# kraken.net
KiCad netlist of a schematic drawn in EAGLE
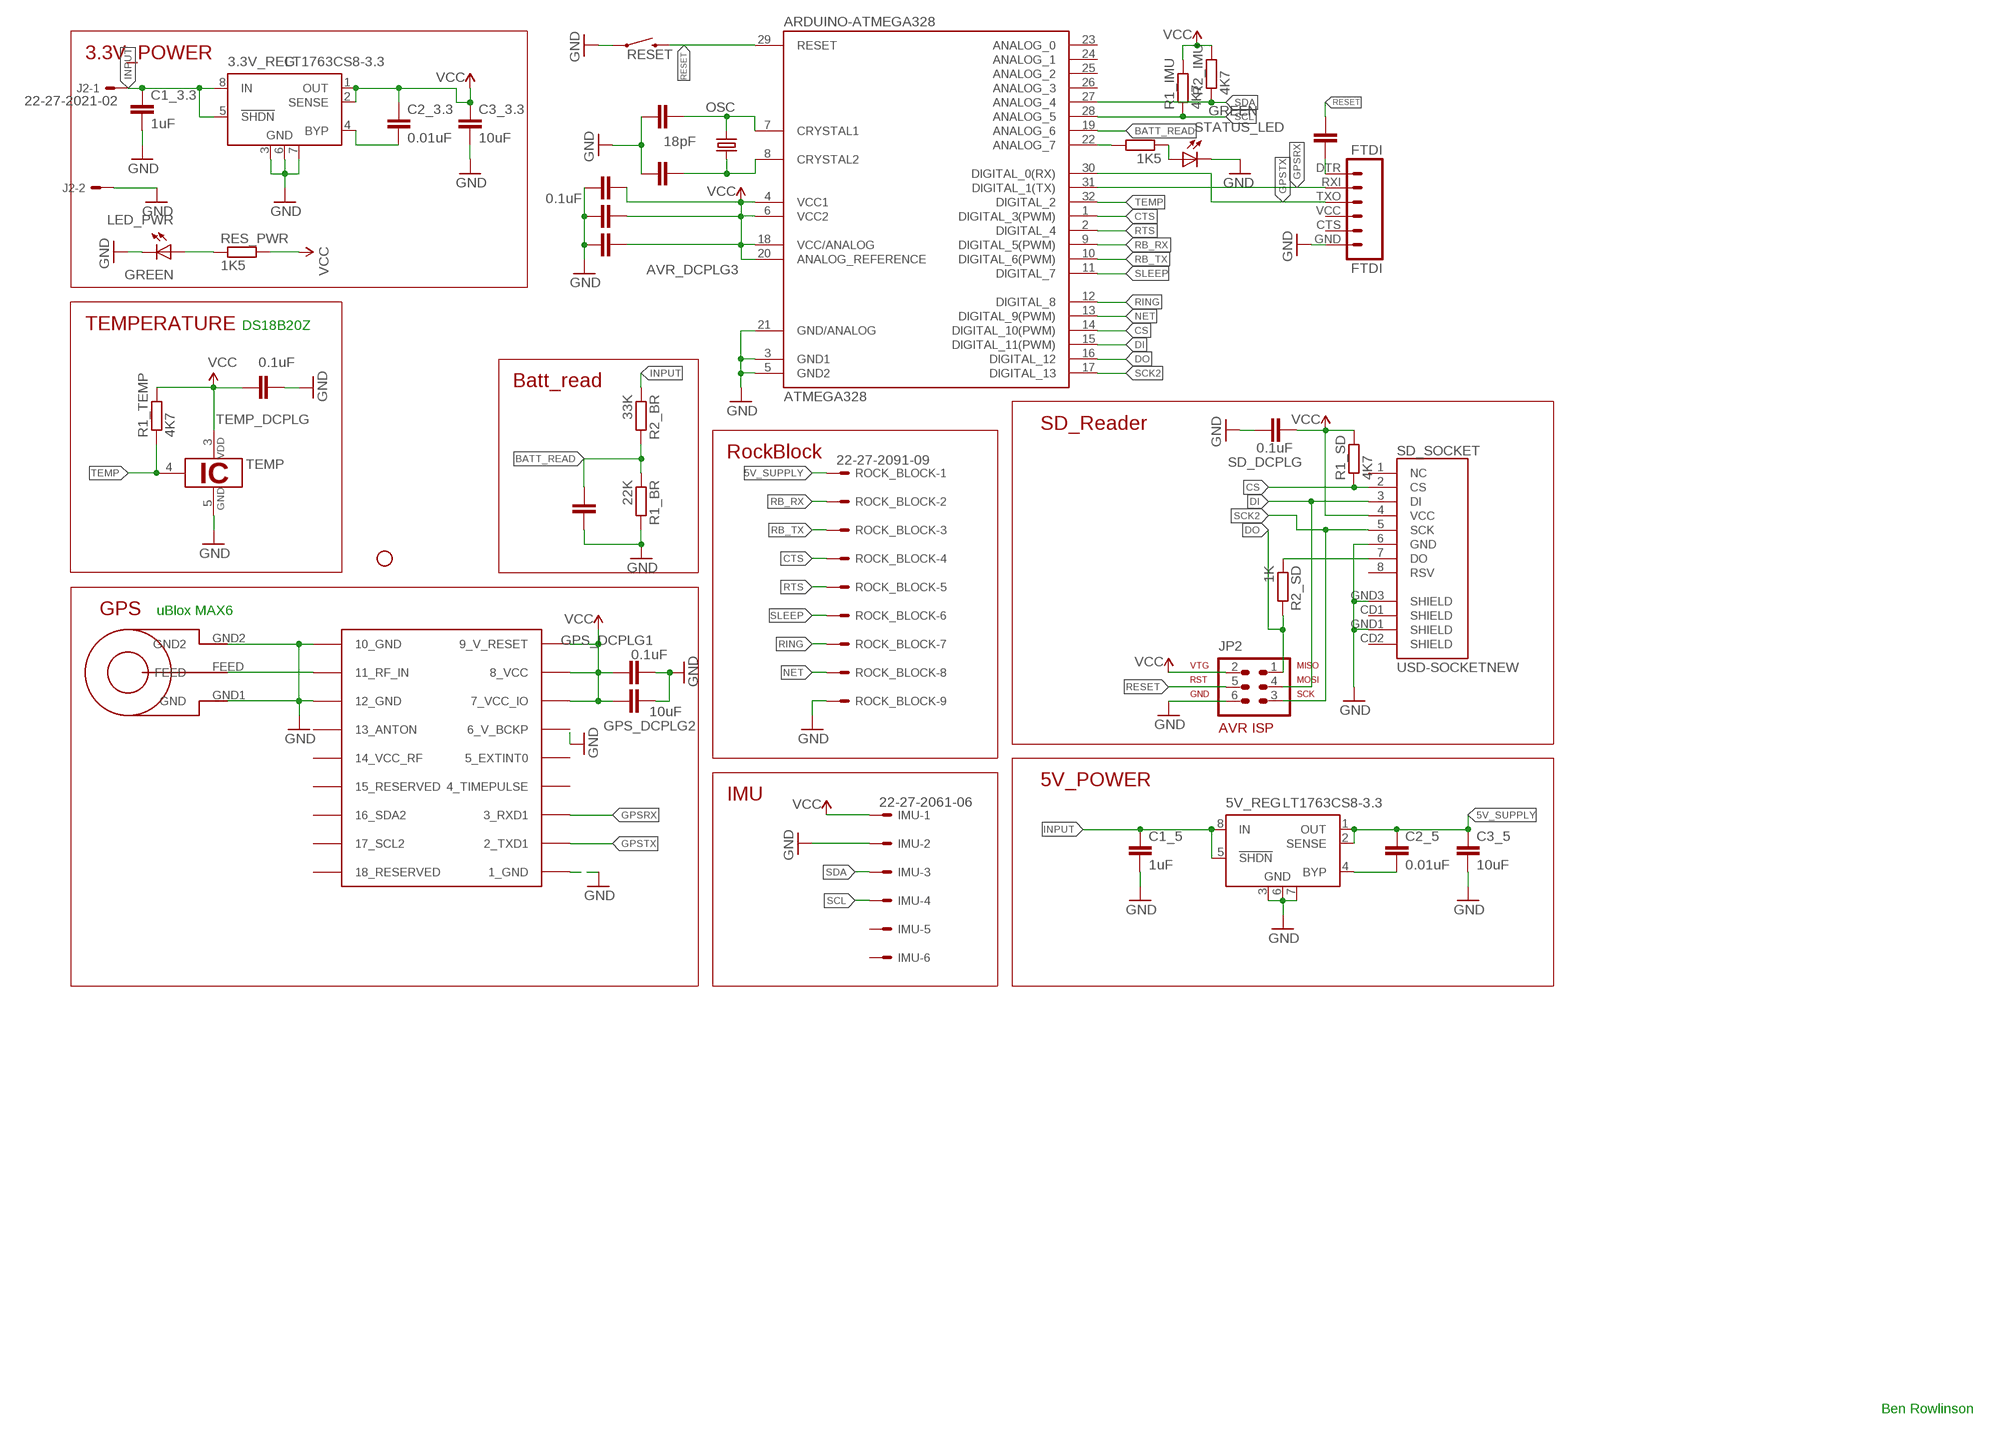
[diagram p0: schematic, sheet 1]

(export (version "E")
  (design (tool "Eeschema 10.0.6"))
  (components
    (comp (ref "3.3V_REG")
      (value "LT1763CS8-3.3")
      (footprint "eagle-import:SOIC8")
      (libsource (lib "eagle-import") (part "LT1763CS8-3.3"))
    )
    (comp (ref "5V_REG")
      (value "LT1763CS8-3.3")
      (footprint "eagle-import:SOIC8")
      (libsource (lib "eagle-import") (part "LT1763CS8-3.3"))
    )
    (comp (ref "ARDUINO-ATMEGA328")
      (value "ATMEGA328")
      (footprint "eagle-import:TQFP32-08")
      (libsource (lib "eagle-import") (part "ATMEGA168-AU"))
    )
    (comp (ref "AVR_DCPLG1")
      (value "0.1uF")
      (footprint "eagle-import:0805")
      (libsource (lib "eagle-import") (part "CAP0805"))
    )
    (comp (ref "AVR_DCPLG2")
      (value "0.1uF")
      (footprint "eagle-import:0805")
      (libsource (lib "eagle-import") (part "CAP0805"))
    )
    (comp (ref "AVR_DCPLG3")
      (value "0.1uF")
      (footprint "eagle-import:0805")
      (libsource (lib "eagle-import") (part "CAP0805"))
    )
    (comp (ref "C1_3.3")
      (value "1uF")
      (footprint "eagle-import:0805")
      (libsource (lib "eagle-import") (part "apex_CAP0805"))
    )
    (comp (ref "C1_5")
      (value "1uF")
      (footprint "eagle-import:0805")
      (libsource (lib "eagle-import") (part "apex_CAP0805"))
    )
    (comp (ref "C1_BR")
      (value "0.1uF")
      (footprint "eagle-import:0805")
      (libsource (lib "eagle-import") (part "CAP0805"))
    )
    (comp (ref "C1_OSC")
      (value "18pF")
      (footprint "eagle-import:0805")
      (libsource (lib "eagle-import") (part "CAP0805"))
    )
    (comp (ref "C2_3.3")
      (value "0.01uF")
      (footprint "eagle-import:0805")
      (libsource (lib "eagle-import") (part "apex_CAP0805"))
    )
    (comp (ref "C2_5")
      (value "0.01uF")
      (footprint "eagle-import:0805")
      (libsource (lib "eagle-import") (part "apex_CAP0805"))
    )
    (comp (ref "C2_OSC")
      (value "18pF")
      (footprint "eagle-import:0805")
      (libsource (lib "eagle-import") (part "CAP0805"))
    )
    (comp (ref "C3_3.3")
      (value "10uF")
      (footprint "eagle-import:0805")
      (libsource (lib "eagle-import") (part "apex_CAP0805"))
    )
    (comp (ref "C3_5")
      (value "10uF")
      (footprint "eagle-import:0805")
      (libsource (lib "eagle-import") (part "apex_CAP0805"))
    )
    (comp (ref "FTDI")
      (value "FTDI")
      (footprint "eagle-import:FTDI_BASIC")
      (libsource (lib "eagle-import") (part "FTDI_BASICPTH"))
    )
    (comp (ref "FTDI_DCPLG")
      (value "0.1uF")
      (footprint "eagle-import:0805")
      (libsource (lib "eagle-import") (part "CAP0805"))
    )
    (comp (ref "GPS_DCPLG1")
      (value "0.1uF")
      (footprint "eagle-import:0805")
      (libsource (lib "eagle-import") (part "CAP0805"))
    )
    (comp (ref "GPS_DCPLG2")
      (value "10uF")
      (footprint "eagle-import:0805")
      (libsource (lib "eagle-import") (part "CAP0805"))
    )
    (comp (ref "IMU")
      (value "22-27-2061-06")
      (footprint "eagle-import:6410-06")
      (libsource (lib "eagle-import") (part "22-?-0627-2061"))
    )
    (comp (ref "J2")
      (value "22-27-2021-02")
      (footprint "eagle-import:6410-02")
      (libsource (lib "eagle-import") (part "22-?-0227-2021"))
    )
    (comp (ref "JP1")
      (value "STAND-OFF")
      (footprint "eagle-import:STAND-OFF")
      (libsource (lib "eagle-import") (part "STAND-OFF"))
    )
    (comp (ref "JP2")
      (value "AVR-ISP-6")
      (footprint "eagle-import:AVR-ISP-6")
      (libsource (lib "eagle-import") (part "AVR-ISP-6"))
    )
    (comp (ref "LED_PWR")
      (value "GREEN")
      (footprint "eagle-import:CHIPLED_0603")
      (libsource (lib "eagle-import") (part "LEDCHIPLED_0603"))
    )
    (comp (ref "OSC")
      (value "16MHz")
      (footprint "eagle-import:CRYSTAL-SMD-5X3")
      (libsource (lib "eagle-import") (part "CRYSTAL5X3"))
    )
    (comp (ref "R1_BR")
      (value "22K")
      (footprint "eagle-import:R0805")
      (libsource (lib "eagle-import") (part "R-EU_R0805"))
    )
    (comp (ref "R1_IMU")
      (value "4K7")
      (footprint "eagle-import:R0805")
      (libsource (lib "eagle-import") (part "R-EU_R0805"))
    )
    (comp (ref "R1_SD")
      (value "4K7")
      (footprint "eagle-import:R0805")
      (libsource (lib "eagle-import") (part "R-EU_R0805"))
    )
    (comp (ref "R1_TEMP")
      (value "4K7")
      (footprint "eagle-import:R0805")
      (libsource (lib "eagle-import") (part "R-EU_R0805"))
    )
    (comp (ref "R2_BR")
      (value "33K")
      (footprint "eagle-import:R0805")
      (libsource (lib "eagle-import") (part "R-EU_R0805"))
    )
    (comp (ref "R2_IMU")
      (value "4K7")
      (footprint "eagle-import:R0805")
      (libsource (lib "eagle-import") (part "R-EU_R0805"))
    )
    (comp (ref "R2_SD")
      (value "1K")
      (footprint "eagle-import:R0805")
      (libsource (lib "eagle-import") (part "R-EU_R0805"))
    )
    (comp (ref "RESET")
      (value "SW-MOMENTARY-SMD")
      (footprint "eagle-import:TACTILE-SWITCH-1101NE")
      (libsource (lib "eagle-import") (part "SWITCH-MOMENTARY-2-SMD-1101NE"))
    )
    (comp (ref "RES_PWR")
      (value "1K5")
      (footprint "eagle-import:R0805")
      (libsource (lib "eagle-import") (part "R-EU_R0805"))
    )
    (comp (ref "ROCK_BLOCK")
      (value "22-27-2091-09")
      (footprint "eagle-import:6410-09")
      (libsource (lib "eagle-import") (part "22-?-0927-2091"))
    )
    (comp (ref "R_STATUS")
      (value "1K5")
      (footprint "eagle-import:R0805")
      (libsource (lib "eagle-import") (part "R-EU_R0805"))
    )
    (comp (ref "SD_DCPLG")
      (value "0.1uF")
      (footprint "eagle-import:0805")
      (libsource (lib "eagle-import") (part "CAP0805"))
    )
    (comp (ref "SD_SOCKET")
      (value "USD-SOCKETNEW")
      (footprint "eagle-import:MICRO-SD-SOCKET-PP")
      (libsource (lib "eagle-import") (part "USD-SOCKETNEW"))
    )
    (comp (ref "STATUS_LED")
      (value "GREEN")
      (footprint "eagle-import:CHIPLED_0603")
      (libsource (lib "eagle-import") (part "LEDCHIPLED_0603"))
    )
    (comp (ref "TEMP")
      (value "DS18B20Z")
      (footprint "eagle-import:SO08")
      (libsource (lib "eagle-import") (part "DS18B20Z"))
    )
    (comp (ref "TEMP_DCPLG")
      (value "0.1uF")
      (footprint "eagle-import:0805")
      (libsource (lib "eagle-import") (part "CAP0805"))
    )
    (comp (ref "U$1")
      (value "UBLOX_MAX-6")
      (footprint "eagle-import:UBLOX_MAX-6")
      (libsource (lib "eagle-import") (part "UBLOX_MAX-6"))
    )
    (comp (ref "U$2")
      (value "SARANTEL-SR1202")
      (footprint "eagle-import:SARANTEL-SR1202")
      (libsource (lib "eagle-import") (part "SARANTEL-SR1202"))
    )
  )
  (nets
    (net (code "1") (name "5V_SUPPLY") (class "Default")
      (node (ref "5V_REG") (pin "1") (pinfunction "OUT_1") (pintype "passive"))
      (node (ref "5V_REG") (pin "2") (pinfunction "SENSE_2") (pintype "input"))
      (node (ref "C2_5") (pin "1") (pinfunction "1_1") (pintype "passive"))
      (node (ref "C3_5") (pin "1") (pinfunction "1_1") (pintype "passive"))
      (node (ref "ROCK_BLOCK") (pin "1") (pinfunction "S_1") (pintype "passive"))
    )
    (net (code "2") (name "BATT_READ") (class "Default")
      (node (ref "ARDUINO-ATMEGA328") (pin "19") (pinfunction "ANALOG_6_19") (pintype "passive"))
      (node (ref "C1_BR") (pin "2") (pinfunction "2_2") (pintype "passive"))
      (node (ref "R1_BR") (pin "1") (pinfunction "1_1") (pintype "passive"))
      (node (ref "R2_BR") (pin "2") (pinfunction "2_2") (pintype "passive"))
    )
    (net (code "3") (name "CS") (class "Default")
      (node (ref "ARDUINO-ATMEGA328") (pin "14") (pinfunction "DIGITAL_10(PWM)_14") (pintype "bidirectional"))
      (node (ref "R1_SD") (pin "1") (pinfunction "1_1") (pintype "passive"))
      (node (ref "SD_SOCKET") (pin "2") (pinfunction "CS_2") (pintype "bidirectional"))
    )
    (net (code "4") (name "CTS") (class "Default")
      (node (ref "ARDUINO-ATMEGA328") (pin "1") (pinfunction "DIGITAL_3(PWM)_1") (pintype "bidirectional"))
      (node (ref "ROCK_BLOCK") (pin "4") (pinfunction "S_4") (pintype "passive"))
    )
    (net (code "5") (name "DI") (class "Default")
      (node (ref "ARDUINO-ATMEGA328") (pin "15") (pinfunction "DIGITAL_11(PWM)_15") (pintype "bidirectional"))
      (node (ref "JP2") (pin "4") (pinfunction "4_4") (pintype "passive"))
      (node (ref "SD_SOCKET") (pin "3") (pinfunction "DI_3") (pintype "bidirectional"))
    )
    (net (code "6") (name "DO") (class "Default")
      (node (ref "ARDUINO-ATMEGA328") (pin "16") (pinfunction "DIGITAL_12_16") (pintype "bidirectional"))
      (node (ref "JP2") (pin "1") (pinfunction "1_1") (pintype "passive"))
      (node (ref "R2_SD") (pin "2") (pinfunction "2_2") (pintype "passive"))
    )
    (net (code "7") (name "GND") (class "Default")
      (node (ref "3.3V_REG") (pin "3") (pinfunction "GND_3") (pintype "power_in"))
      (node (ref "3.3V_REG") (pin "6") (pinfunction "GND_6") (pintype "power_in"))
      (node (ref "3.3V_REG") (pin "7") (pinfunction "GND_7") (pintype "power_in"))
      (node (ref "5V_REG") (pin "3") (pinfunction "GND_3") (pintype "power_in"))
      (node (ref "5V_REG") (pin "6") (pinfunction "GND_6") (pintype "power_in"))
      (node (ref "5V_REG") (pin "7") (pinfunction "GND_7") (pintype "power_in"))
      (node (ref "ARDUINO-ATMEGA328") (pin "21") (pinfunction "GND/ANALOG_21") (pintype "power_in"))
      (node (ref "ARDUINO-ATMEGA328") (pin "3") (pinfunction "GND1_3") (pintype "power_in"))
      (node (ref "ARDUINO-ATMEGA328") (pin "5") (pinfunction "GND2_5") (pintype "power_in"))
      (node (ref "AVR_DCPLG1") (pin "1") (pinfunction "1_1") (pintype "passive"))
      (node (ref "AVR_DCPLG2") (pin "1") (pinfunction "1_1") (pintype "passive"))
      (node (ref "AVR_DCPLG3") (pin "1") (pinfunction "1_1") (pintype "passive"))
      (node (ref "C1_3.3") (pin "2") (pinfunction "2_2") (pintype "passive"))
      (node (ref "C1_5") (pin "2") (pinfunction "2_2") (pintype "passive"))
      (node (ref "C1_BR") (pin "1") (pinfunction "1_1") (pintype "passive"))
      (node (ref "C1_OSC") (pin "1") (pinfunction "1_1") (pintype "passive"))
      (node (ref "C2_OSC") (pin "1") (pinfunction "1_1") (pintype "passive"))
      (node (ref "C3_3.3") (pin "2") (pinfunction "2_2") (pintype "passive"))
      (node (ref "C3_5") (pin "2") (pinfunction "2_2") (pintype "passive"))
      (node (ref "FTDI") (pin "GND") (pinfunction "6_GND") (pintype "passive"))
      (node (ref "GPS_DCPLG1") (pin "2") (pinfunction "2_2") (pintype "passive"))
      (node (ref "GPS_DCPLG2") (pin "2") (pinfunction "2_2") (pintype "passive"))
      (node (ref "IMU") (pin "2") (pinfunction "S_2") (pintype "passive"))
      (node (ref "J2") (pin "2") (pinfunction "S_2") (pintype "passive"))
      (node (ref "JP2") (pin "6") (pinfunction "6_6") (pintype "passive"))
      (node (ref "LED_PWR") (pin "C") (pinfunction "C_C") (pintype "passive"))
      (node (ref "R1_BR") (pin "2") (pinfunction "2_2") (pintype "passive"))
      (node (ref "RESET") (pin "P$1") (pinfunction "1_P$1") (pintype "passive"))
      (node (ref "ROCK_BLOCK") (pin "9") (pinfunction "S_9") (pintype "passive"))
      (node (ref "SD_DCPLG") (pin "2") (pinfunction "2_2") (pintype "passive"))
      (node (ref "SD_SOCKET") (pin "6") (pinfunction "GND_6") (pintype "bidirectional"))
      (node (ref "SD_SOCKET") (pin "GND1") (pinfunction "SHIELD_GND1") (pintype "bidirectional"))
      (node (ref "SD_SOCKET") (pin "GND3") (pinfunction "SHIELD_GND3") (pintype "bidirectional"))
      (node (ref "STATUS_LED") (pin "C") (pinfunction "C_C") (pintype "passive"))
      (node (ref "TEMP") (pin "5") (pinfunction "GND_5") (pintype "power_in"))
      (node (ref "TEMP_DCPLG") (pin "1") (pinfunction "1_1") (pintype "passive"))
      (node (ref "U$1") (pin "10_GND") (pinfunction "10_GND_10_GND") (pintype "power_in"))
      (node (ref "U$1") (pin "12_GND") (pinfunction "12_GND_12_GND") (pintype "power_in"))
      (node (ref "U$1") (pin "1_GND") (pinfunction "1_GND_1_GND") (pintype "power_in"))
      (node (ref "U$1") (pin "6_V_BCKP") (pinfunction "6_V_BCKP_6_V_BCKP") (pintype "bidirectional"))
      (node (ref "U$2") (pin "GND1") (pinfunction "GND_GND1") (pintype "bidirectional"))
      (node (ref "U$2") (pin "GND2") (pinfunction "GND2_GND2") (pintype "bidirectional"))
    )
    (net (code "8") (name "GPSRX") (class "Default")
      (node (ref "ARDUINO-ATMEGA328") (pin "31") (pinfunction "DIGITAL_1(TX)_31") (pintype "bidirectional"))
      (node (ref "FTDI") (pin "RXI") (pinfunction "2_RXI") (pintype "passive"))
      (node (ref "U$1") (pin "3_RXD1") (pinfunction "3_RXD1_3_RXD1") (pintype "bidirectional"))
    )
    (net (code "9") (name "GPSTX") (class "Default")
      (node (ref "ARDUINO-ATMEGA328") (pin "30") (pinfunction "DIGITAL_0(RX)_30") (pintype "bidirectional"))
      (node (ref "FTDI") (pin "TXO") (pinfunction "3_TXO") (pintype "passive"))
      (node (ref "U$1") (pin "2_TXD1") (pinfunction "2_TXD1_2_TXD1") (pintype "bidirectional"))
    )
    (net (code "10") (name "INPUT") (class "Default")
      (node (ref "3.3V_REG") (pin "5") (pinfunction "~{SHDN}_5") (pintype "input"))
      (node (ref "3.3V_REG") (pin "8") (pinfunction "IN_8") (pintype "input"))
      (node (ref "5V_REG") (pin "5") (pinfunction "~{SHDN}_5") (pintype "input"))
      (node (ref "5V_REG") (pin "8") (pinfunction "IN_8") (pintype "input"))
      (node (ref "C1_3.3") (pin "1") (pinfunction "1_1") (pintype "passive"))
      (node (ref "C1_5") (pin "1") (pinfunction "1_1") (pintype "passive"))
      (node (ref "J2") (pin "1") (pinfunction "S_1") (pintype "passive"))
      (node (ref "R2_BR") (pin "1") (pinfunction "1_1") (pintype "passive"))
    )
    (net (code "11") (name "NET") (class "Default")
      (node (ref "ARDUINO-ATMEGA328") (pin "13") (pinfunction "DIGITAL_9(PWM)_13") (pintype "bidirectional"))
      (node (ref "ROCK_BLOCK") (pin "8") (pinfunction "S_8") (pintype "passive"))
    )
    (net (code "12") (name "Net-(3.3V_REG-BYP)") (class "Default")
      (node (ref "3.3V_REG") (pin "4") (pinfunction "BYP_4") (pintype "input"))
      (node (ref "C2_3.3") (pin "2") (pinfunction "2_2") (pintype "passive"))
    )
    (net (code "13") (name "Net-(5V_REG-BYP)") (class "Default")
      (node (ref "5V_REG") (pin "4") (pinfunction "BYP_4") (pintype "input"))
      (node (ref "C2_5") (pin "2") (pinfunction "2_2") (pintype "passive"))
    )
    (net (code "14") (name "Net-(ARDUINO-ATMEGA328-ANALOG_7)") (class "Default")
      (node (ref "ARDUINO-ATMEGA328") (pin "22") (pinfunction "ANALOG_7_22") (pintype "passive"))
      (node (ref "R_STATUS") (pin "2") (pinfunction "2_2") (pintype "passive"))
    )
    (net (code "15") (name "Net-(ARDUINO-ATMEGA328-CRYSTAL1)") (class "Default")
      (node (ref "ARDUINO-ATMEGA328") (pin "7") (pinfunction "CRYSTAL1_7") (pintype "bidirectional"))
      (node (ref "C1_OSC") (pin "2") (pinfunction "2_2") (pintype "passive"))
      (node (ref "OSC") (pin "3") (pinfunction "2_3") (pintype "passive"))
    )
    (net (code "16") (name "Net-(ARDUINO-ATMEGA328-CRYSTAL2)") (class "Default")
      (node (ref "ARDUINO-ATMEGA328") (pin "8") (pinfunction "CRYSTAL2_8") (pintype "bidirectional"))
      (node (ref "C2_OSC") (pin "2") (pinfunction "2_2") (pintype "passive"))
      (node (ref "OSC") (pin "1") (pinfunction "1_1") (pintype "passive"))
    )
    (net (code "17") (name "Net-(FTDI-1)") (class "Default")
      (node (ref "FTDI") (pin "DTR") (pinfunction "1_DTR") (pintype "passive"))
      (node (ref "FTDI_DCPLG") (pin "2") (pinfunction "2_2") (pintype "passive"))
    )
    (net (code "18") (name "Net-(LED_PWR-PadA)") (class "Default")
      (node (ref "LED_PWR") (pin "A") (pinfunction "A_A") (pintype "passive"))
      (node (ref "RES_PWR") (pin "1") (pinfunction "1_1") (pintype "passive"))
    )
    (net (code "19") (name "Net-(R_STATUS-Pad1)") (class "Default")
      (node (ref "R_STATUS") (pin "1") (pinfunction "1_1") (pintype "passive"))
      (node (ref "STATUS_LED") (pin "A") (pinfunction "A_A") (pintype "passive"))
    )
    (net (code "20") (name "Net-(SD_SOCKET-DO)") (class "Default")
      (node (ref "R2_SD") (pin "1") (pinfunction "1_1") (pintype "passive"))
      (node (ref "SD_SOCKET") (pin "7") (pinfunction "DO_7") (pintype "bidirectional"))
    )
    (net (code "21") (name "Net-(U$1-Pad11_RF_IN)") (class "Default")
      (node (ref "U$1") (pin "11_RF_IN") (pinfunction "11_RF_IN_11_RF_IN") (pintype "bidirectional"))
      (node (ref "U$2") (pin "FEED") (pinfunction "FEED_FEED") (pintype "bidirectional"))
    )
    (net (code "22") (name "RB_RX") (class "Default")
      (node (ref "ARDUINO-ATMEGA328") (pin "9") (pinfunction "DIGITAL_5(PWM)_9") (pintype "bidirectional"))
      (node (ref "ROCK_BLOCK") (pin "2") (pinfunction "S_2") (pintype "passive"))
    )
    (net (code "23") (name "RB_TX") (class "Default")
      (node (ref "ARDUINO-ATMEGA328") (pin "10") (pinfunction "DIGITAL_6(PWM)_10") (pintype "bidirectional"))
      (node (ref "ROCK_BLOCK") (pin "3") (pinfunction "S_3") (pintype "passive"))
    )
    (net (code "24") (name "RESET") (class "Default")
      (node (ref "ARDUINO-ATMEGA328") (pin "29") (pinfunction "RESET_29") (pintype "bidirectional"))
      (node (ref "FTDI_DCPLG") (pin "1") (pinfunction "1_1") (pintype "passive"))
      (node (ref "JP2") (pin "5") (pinfunction "5_5") (pintype "passive"))
      (node (ref "RESET") (pin "P$2") (pinfunction "2_P$2") (pintype "passive"))
    )
    (net (code "25") (name "RING") (class "Default")
      (node (ref "ARDUINO-ATMEGA328") (pin "12") (pinfunction "DIGITAL_8_12") (pintype "bidirectional"))
      (node (ref "ROCK_BLOCK") (pin "7") (pinfunction "S_7") (pintype "passive"))
    )
    (net (code "26") (name "RTS") (class "Default")
      (node (ref "ARDUINO-ATMEGA328") (pin "2") (pinfunction "DIGITAL_4_2") (pintype "bidirectional"))
      (node (ref "ROCK_BLOCK") (pin "5") (pinfunction "S_5") (pintype "passive"))
    )
    (net (code "27") (name "SCK2") (class "Default")
      (node (ref "ARDUINO-ATMEGA328") (pin "17") (pinfunction "DIGITAL_13_17") (pintype "bidirectional"))
      (node (ref "JP2") (pin "3") (pinfunction "3_3") (pintype "passive"))
      (node (ref "SD_SOCKET") (pin "5") (pinfunction "SCK_5") (pintype "bidirectional"))
    )
    (net (code "28") (name "SCL") (class "Default")
      (node (ref "ARDUINO-ATMEGA328") (pin "28") (pinfunction "ANALOG_5_28") (pintype "bidirectional"))
      (node (ref "IMU") (pin "4") (pinfunction "S_4") (pintype "passive"))
      (node (ref "R1_IMU") (pin "1") (pinfunction "1_1") (pintype "passive"))
    )
    (net (code "29") (name "SDA") (class "Default")
      (node (ref "ARDUINO-ATMEGA328") (pin "27") (pinfunction "ANALOG_4_27") (pintype "bidirectional"))
      (node (ref "IMU") (pin "3") (pinfunction "S_3") (pintype "passive"))
      (node (ref "R2_IMU") (pin "1") (pinfunction "1_1") (pintype "passive"))
    )
    (net (code "30") (name "SLEEP") (class "Default")
      (node (ref "ARDUINO-ATMEGA328") (pin "11") (pinfunction "DIGITAL_7_11") (pintype "bidirectional"))
      (node (ref "ROCK_BLOCK") (pin "6") (pinfunction "S_6") (pintype "passive"))
    )
    (net (code "31") (name "TEMP") (class "Default")
      (node (ref "ARDUINO-ATMEGA328") (pin "32") (pinfunction "DIGITAL_2_32") (pintype "bidirectional"))
      (node (ref "R1_TEMP") (pin "1") (pinfunction "1_1") (pintype "passive"))
      (node (ref "TEMP") (pin "4") (pinfunction "1W_4") (pintype "power_in"))
    )
    (net (code "32") (name "VCC") (class "Default")
      (node (ref "3.3V_REG") (pin "1") (pinfunction "OUT_1") (pintype "passive"))
      (node (ref "3.3V_REG") (pin "2") (pinfunction "SENSE_2") (pintype "input"))
      (node (ref "ARDUINO-ATMEGA328") (pin "18") (pinfunction "VCC/ANALOG_18") (pintype "passive"))
      (node (ref "ARDUINO-ATMEGA328") (pin "20") (pinfunction "ANALOG_REFERENCE_20") (pintype "passive"))
      (node (ref "ARDUINO-ATMEGA328") (pin "4") (pinfunction "VCC1_4") (pintype "power_in"))
      (node (ref "ARDUINO-ATMEGA328") (pin "6") (pinfunction "VCC2_6") (pintype "power_in"))
      (node (ref "AVR_DCPLG1") (pin "2") (pinfunction "2_2") (pintype "passive"))
      (node (ref "AVR_DCPLG2") (pin "2") (pinfunction "2_2") (pintype "passive"))
      (node (ref "AVR_DCPLG3") (pin "2") (pinfunction "2_2") (pintype "passive"))
      (node (ref "C2_3.3") (pin "1") (pinfunction "1_1") (pintype "passive"))
      (node (ref "C3_3.3") (pin "1") (pinfunction "1_1") (pintype "passive"))
      (node (ref "GPS_DCPLG1") (pin "1") (pinfunction "1_1") (pintype "passive"))
      (node (ref "GPS_DCPLG2") (pin "1") (pinfunction "1_1") (pintype "passive"))
      (node (ref "IMU") (pin "1") (pinfunction "S_1") (pintype "passive"))
      (node (ref "JP2") (pin "2") (pinfunction "2_2") (pintype "passive"))
      (node (ref "R1_IMU") (pin "2") (pinfunction "2_2") (pintype "passive"))
      (node (ref "R1_SD") (pin "2") (pinfunction "2_2") (pintype "passive"))
      (node (ref "R1_TEMP") (pin "2") (pinfunction "2_2") (pintype "passive"))
      (node (ref "R2_IMU") (pin "2") (pinfunction "2_2") (pintype "passive"))
      (node (ref "RES_PWR") (pin "2") (pinfunction "2_2") (pintype "passive"))
      (node (ref "SD_DCPLG") (pin "1") (pinfunction "1_1") (pintype "passive"))
      (node (ref "SD_SOCKET") (pin "4") (pinfunction "VCC_4") (pintype "bidirectional"))
      (node (ref "TEMP") (pin "3") (pinfunction "VDD_3") (pintype "power_in"))
      (node (ref "TEMP_DCPLG") (pin "2") (pinfunction "2_2") (pintype "passive"))
      (node (ref "U$1") (pin "7_VCC_IO") (pinfunction "7_VCC_IO_7_VCC_IO") (pintype "power_in"))
      (node (ref "U$1") (pin "8_VCC") (pinfunction "8_VCC_8_VCC") (pintype "power_in"))
      (node (ref "U$1") (pin "9_V_RESET") (pinfunction "9_V_RESET_9_V_RESET") (pintype "power_in"))
    )
    (net (code "33") (name "unconnected-(ARDUINO-ATMEGA328-ANALOG_0-Pad23)") (class "Default")
      (node (ref "ARDUINO-ATMEGA328") (pin "23") (pinfunction "ANALOG_0_23") (pintype "bidirectional"))
    )
    (net (code "34") (name "unconnected-(ARDUINO-ATMEGA328-ANALOG_1-Pad24)") (class "Default")
      (node (ref "ARDUINO-ATMEGA328") (pin "24") (pinfunction "ANALOG_1_24") (pintype "bidirectional"))
    )
    (net (code "35") (name "unconnected-(ARDUINO-ATMEGA328-ANALOG_2-Pad25)") (class "Default")
      (node (ref "ARDUINO-ATMEGA328") (pin "25") (pinfunction "ANALOG_2_25") (pintype "bidirectional"))
    )
    (net (code "36") (name "unconnected-(ARDUINO-ATMEGA328-ANALOG_3-Pad26)") (class "Default")
      (node (ref "ARDUINO-ATMEGA328") (pin "26") (pinfunction "ANALOG_3_26") (pintype "bidirectional"))
    )
    (net (code "37") (name "unconnected-(FTDI-4-PadVCC)") (class "Default")
      (node (ref "FTDI") (pin "VCC") (pinfunction "4_VCC") (pintype "passive"))
    )
    (net (code "38") (name "unconnected-(FTDI-5-PadCTS)") (class "Default")
      (node (ref "FTDI") (pin "CTS") (pinfunction "5_CTS") (pintype "passive"))
    )
    (net (code "39") (name "unconnected-(IMUE-S-Pad5)") (class "Default")
      (node (ref "IMU") (pin "5") (pinfunction "S_5") (pintype "passive"))
    )
    (net (code "40") (name "unconnected-(IMUF-S-Pad6)") (class "Default")
      (node (ref "IMU") (pin "6") (pinfunction "S_6") (pintype "passive"))
    )
    (net (code "41") (name "unconnected-(SD_SOCKET-NC-Pad1)") (class "Default")
      (node (ref "SD_SOCKET") (pin "1") (pinfunction "NC_1") (pintype "bidirectional"))
    )
    (net (code "42") (name "unconnected-(SD_SOCKET-RSV-Pad8)") (class "Default")
      (node (ref "SD_SOCKET") (pin "8") (pinfunction "RSV_8") (pintype "bidirectional"))
    )
    (net (code "43") (name "unconnected-(SD_SOCKET-SHIELD-PadCD1)") (class "Default")
      (node (ref "SD_SOCKET") (pin "CD1") (pinfunction "SHIELD_CD1") (pintype "bidirectional"))
    )
    (net (code "44") (name "unconnected-(SD_SOCKET-SHIELD-PadCD2)") (class "Default")
      (node (ref "SD_SOCKET") (pin "CD2") (pinfunction "SHIELD_CD2") (pintype "bidirectional"))
    )
    (net (code "45") (name "unconnected-(U$1-Pad4_TIMEPULSE)") (class "Default")
      (node (ref "U$1") (pin "4_TIMEPULSE") (pinfunction "4_TIMEPULSE_4_TIMEPULSE") (pintype "bidirectional"))
    )
    (net (code "46") (name "unconnected-(U$1-Pad5_EXTINT0)") (class "Default")
      (node (ref "U$1") (pin "5_EXTINT0") (pinfunction "5_EXTINT0_5_EXTINT0") (pintype "bidirectional"))
    )
    (net (code "47") (name "unconnected-(U$1-Pad13_ANTON)") (class "Default")
      (node (ref "U$1") (pin "13_ANTON") (pinfunction "13_ANTON_13_ANTON") (pintype "bidirectional"))
    )
    (net (code "48") (name "unconnected-(U$1-Pad14_VCC_RF)") (class "Default")
      (node (ref "U$1") (pin "14_VCC_RF") (pinfunction "14_VCC_RF_14_VCC_RF") (pintype "bidirectional"))
    )
    (net (code "49") (name "unconnected-(U$1-Pad15_RESERVED)") (class "Default")
      (node (ref "U$1") (pin "15_RESERVED") (pinfunction "15_RESERVED_15_RESERVED") (pintype "bidirectional"))
    )
    (net (code "50") (name "unconnected-(U$1-Pad16_SDA2)") (class "Default")
      (node (ref "U$1") (pin "16_SDA2") (pinfunction "16_SDA2_16_SDA2") (pintype "bidirectional"))
    )
    (net (code "51") (name "unconnected-(U$1-Pad17_SCL2)") (class "Default")
      (node (ref "U$1") (pin "17_SCL2") (pinfunction "17_SCL2_17_SCL2") (pintype "bidirectional"))
    )
    (net (code "52") (name "unconnected-(U$1-Pad18_RESERVED)") (class "Default")
      (node (ref "U$1") (pin "18_RESERVED") (pinfunction "18_RESERVED_18_RESERVED") (pintype "bidirectional"))
    )
  )
)
